# ATSAM3X8E_Main_Controller_-_TR.net
KiCad netlist of a schematic drawn in Altium Designer
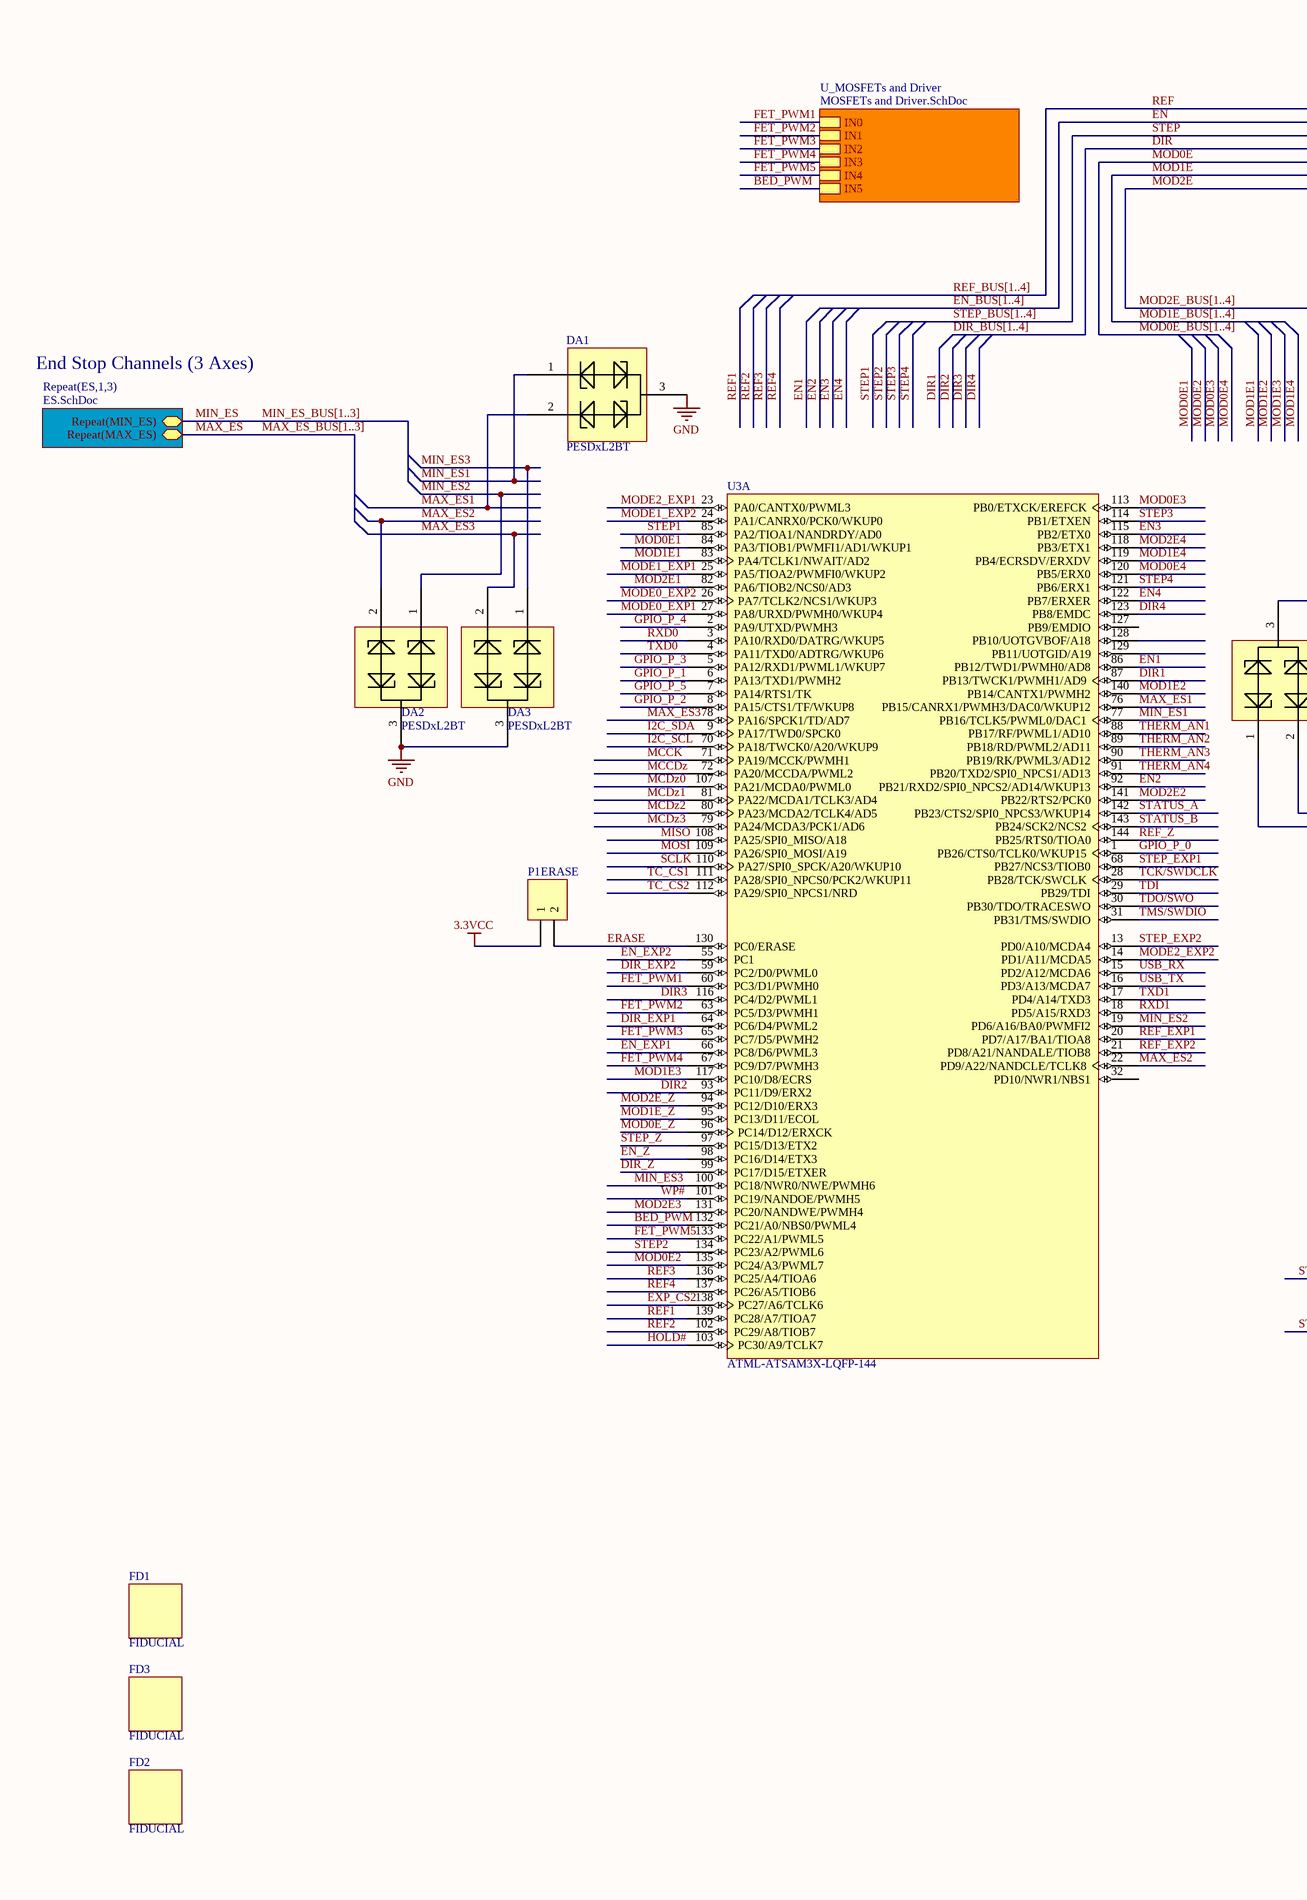
[diagram p0: ATSAM3X8E Main Controller - TR.SchDoc, left]
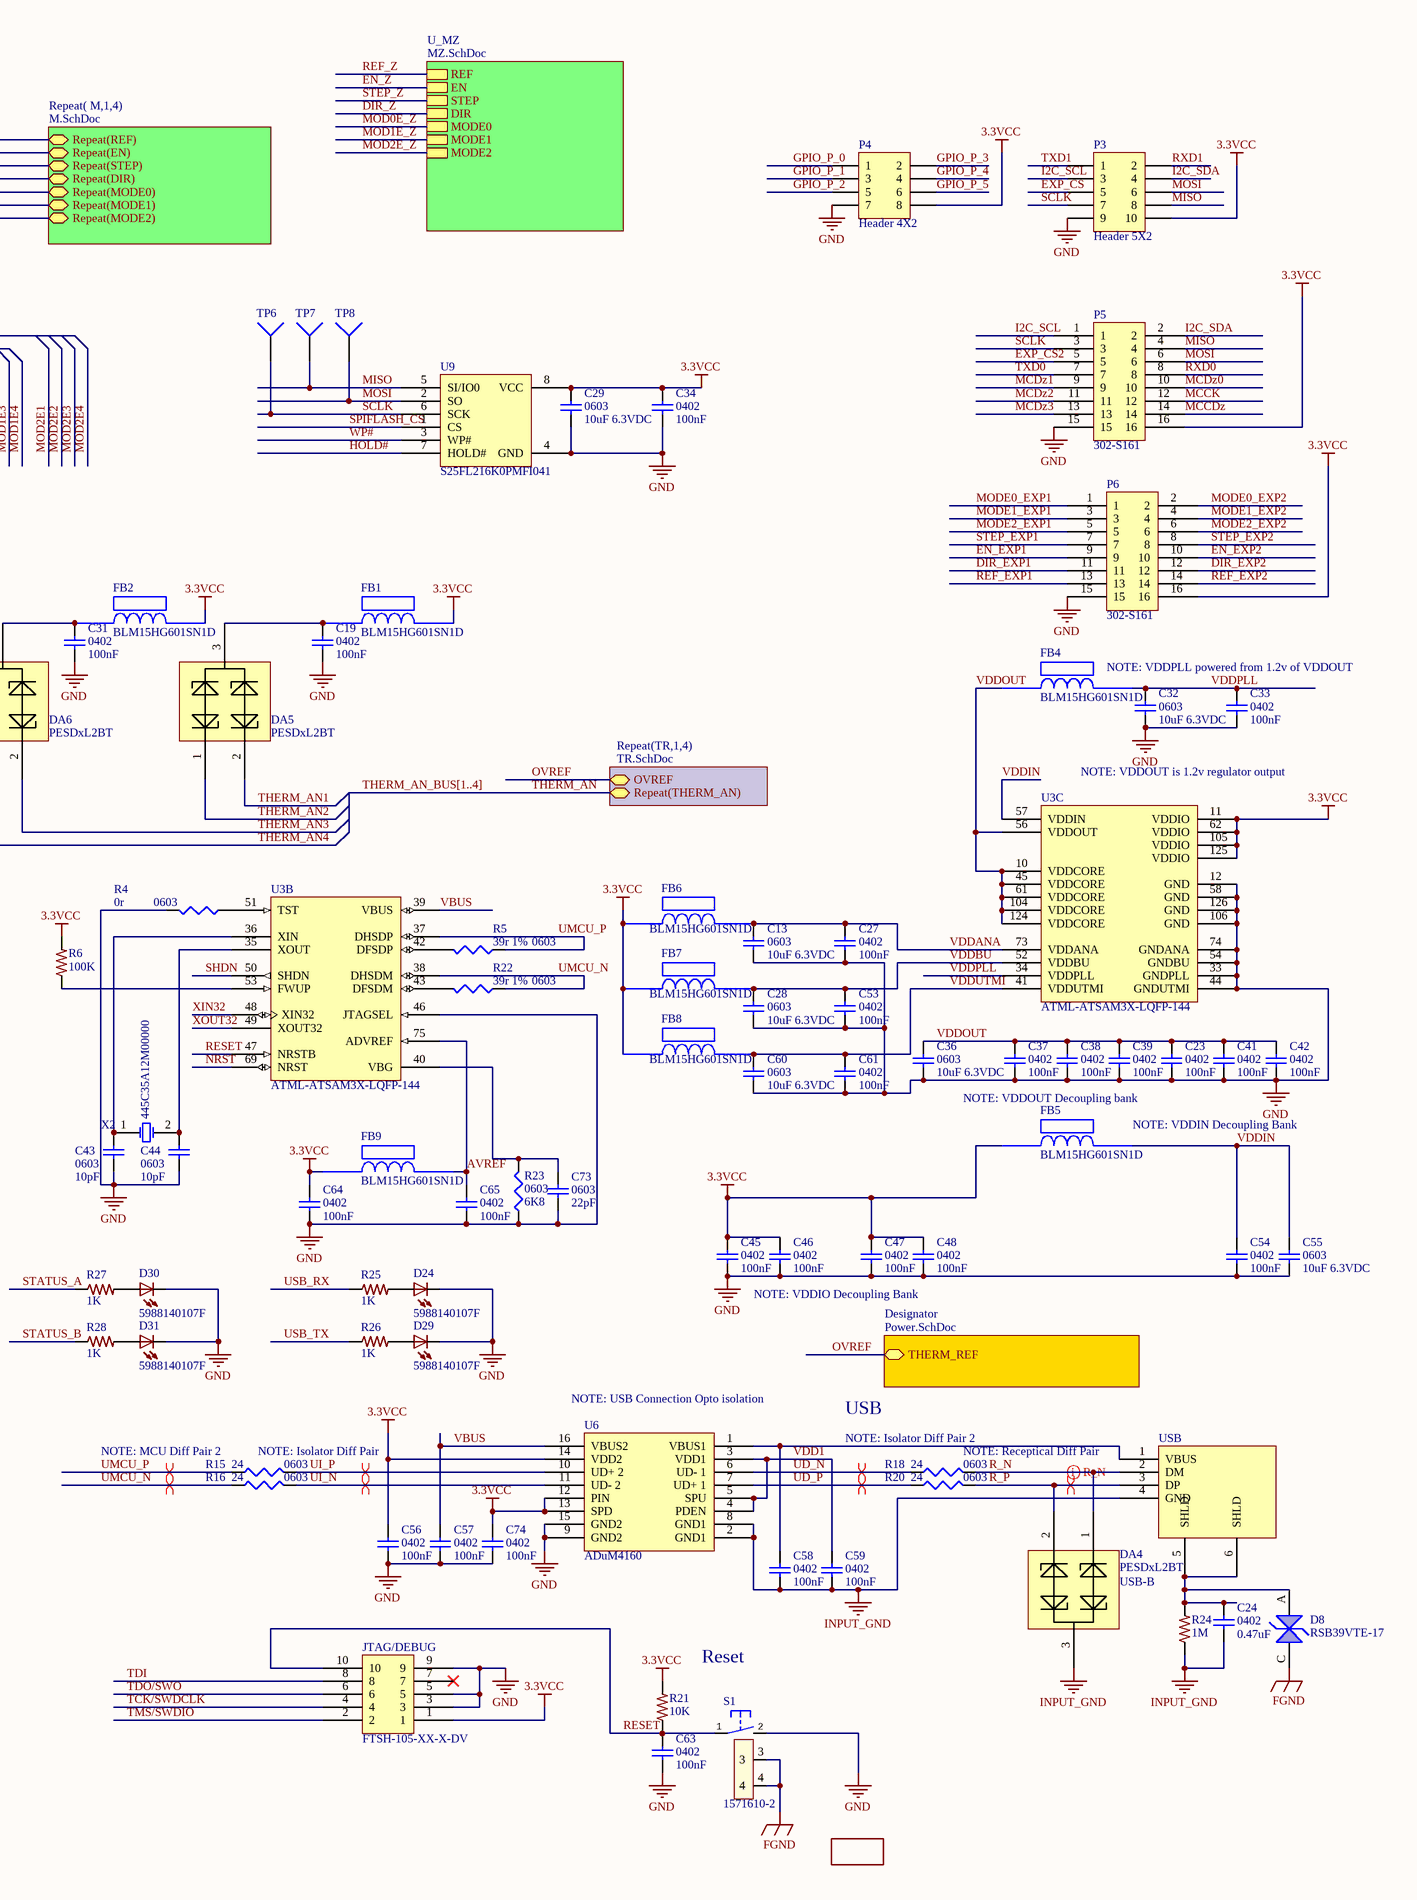
[diagram p1: ATSAM3X8E Main Controller - TR.SchDoc, right]

(export (version "E")
  (design (tool "Eeschema 10.0.6"))
  (components
    (comp (ref "C13")
      (value "0603")
      (footprint "C0603")
      (description "CAP CER 10UF 6.3V 10% JB 0603")
      (fields
        (field (name "MFR PART #") "C1608JB0J106K080AB")
        (field (name "MFR") "TDK")
        (field (name "ALTIUM_VALUE") "10uF 6.3VDC")
      )
      (libsource (lib "Tigershark3D") (part "C1608JB0J106K080AB"))
    )
    (comp (ref "C19")
      (value "100nF")
      (footprint "C0402")
      (description "Capacitor (Semiconductor SIM Model)")
      (fields
        (field (name "MFR PART #") "GRM155R71C104KA88D")
        (field (name "MFR") "Murata")
        (field (name "PACKAGEREFERENCE") "0402")
        (field (name "PUBLISHER") "Ultimachine")
      )
      (libsource (lib "Tigershark3D") (part "100nF C0402 - GRM155R71C104KA88D"))
    )
    (comp (ref "C23")
      (value "100nF")
      (footprint "C0402")
      (description "Capacitor (Semiconductor SIM Model)")
      (fields
        (field (name "MFR PART #") "GRM155R71C104KA88D")
        (field (name "MFR") "Murata")
        (field (name "PACKAGEREFERENCE") "0402")
        (field (name "PUBLISHER") "Ultimachine")
      )
      (libsource (lib "Tigershark3D") (part "100nF C0402 - GRM155R71C104KA88D"))
    )
    (comp (ref "C24")
      (value "0.47uF")
      (footprint "C0402")
      (description "0.47uF 6.3v C0402 - GRM155R60J474KE19D")
      (fields
        (field (name "MFR PART #") "GRM155R60J474KE19D")
        (field (name "MFR") "Murata")
        (field (name "PACKAGEREFERENCE") "0402")
        (field (name "PUBLISHER") "Ultimachine")
      )
      (libsource (lib "Tigershark3D") (part "GRM155R60J474KE19D"))
    )
    (comp (ref "C27")
      (value "100nF")
      (footprint "C0402")
      (description "Capacitor (Semiconductor SIM Model)")
      (fields
        (field (name "MFR PART #") "GRM155R71C104KA88D")
        (field (name "MFR") "Murata")
        (field (name "PACKAGEREFERENCE") "0402")
        (field (name "PUBLISHER") "Ultimachine")
      )
      (libsource (lib "Tigershark3D") (part "100nF C0402 - GRM155R71C104KA88D"))
    )
    (comp (ref "C28")
      (value "0603")
      (footprint "C0603")
      (description "CAP CER 10UF 6.3V 10% JB 0603")
      (fields
        (field (name "MFR PART #") "C1608JB0J106K080AB")
        (field (name "MFR") "TDK")
        (field (name "ALTIUM_VALUE") "10uF 6.3VDC")
      )
      (libsource (lib "Tigershark3D") (part "C1608JB0J106K080AB"))
    )
    (comp (ref "C29")
      (value "0603")
      (footprint "C0603")
      (description "CAP CER 10UF 6.3V 10% JB 0603")
      (fields
        (field (name "MFR PART #") "C1608JB0J106K080AB")
        (field (name "MFR") "TDK")
        (field (name "ALTIUM_VALUE") "10uF 6.3VDC")
      )
      (libsource (lib "Tigershark3D") (part "C1608JB0J106K080AB"))
    )
    (comp (ref "C31")
      (value "100nF")
      (footprint "C0402")
      (description "Capacitor (Semiconductor SIM Model)")
      (fields
        (field (name "MFR PART #") "GRM155R71C104KA88D")
        (field (name "MFR") "Murata")
        (field (name "PACKAGEREFERENCE") "0402")
        (field (name "PUBLISHER") "Ultimachine")
      )
      (libsource (lib "Tigershark3D") (part "100nF C0402 - GRM155R71C104KA88D"))
    )
    (comp (ref "C32")
      (value "0603")
      (footprint "C0603")
      (description "CAP CER 10UF 6.3V 10% JB 0603")
      (fields
        (field (name "MFR PART #") "C1608JB0J106K080AB")
        (field (name "MFR") "TDK")
        (field (name "ALTIUM_VALUE") "10uF 6.3VDC")
      )
      (libsource (lib "Tigershark3D") (part "C1608JB0J106K080AB"))
    )
    (comp (ref "C33")
      (value "100nF")
      (footprint "C0402")
      (description "Capacitor (Semiconductor SIM Model)")
      (fields
        (field (name "MFR PART #") "GRM155R71C104KA88D")
        (field (name "MFR") "Murata")
        (field (name "PACKAGEREFERENCE") "0402")
        (field (name "PUBLISHER") "Ultimachine")
      )
      (libsource (lib "Tigershark3D") (part "100nF C0402 - GRM155R71C104KA88D"))
    )
    (comp (ref "C34")
      (value "100nF")
      (footprint "C0402")
      (description "CAP CER 0.1UF (100nF) 16V 10% X7R 0402")
      (fields
        (field (name "MFR PART #") "GRM155R71C104KA88D")
        (field (name "MFR") "Murata")
        (field (name "PACKAGEREFERENCE") "0402")
        (field (name "PUBLISHER") "Ultimachine")
      )
      (libsource (lib "Tigershark3D") (part "GRM155R71C104KA88D"))
    )
    (comp (ref "C36")
      (value "0603")
      (footprint "C0603")
      (description "CAP CER 10UF 6.3V 10% JB 0603")
      (fields
        (field (name "MFR PART #") "C1608JB0J106K080AB")
        (field (name "MFR") "TDK")
        (field (name "ALTIUM_VALUE") "10uF 6.3VDC")
      )
      (libsource (lib "Tigershark3D") (part "C1608JB0J106K080AB"))
    )
    (comp (ref "C37")
      (value "100nF")
      (footprint "C0402")
      (description "Capacitor (Semiconductor SIM Model)")
      (fields
        (field (name "MFR PART #") "GRM155R71C104KA88D")
        (field (name "MFR") "Murata")
        (field (name "PACKAGEREFERENCE") "0402")
        (field (name "PUBLISHER") "Ultimachine")
      )
      (libsource (lib "Tigershark3D") (part "100nF C0402 - GRM155R71C104KA88D"))
    )
    (comp (ref "C38")
      (value "100nF")
      (footprint "C0402")
      (description "Capacitor (Semiconductor SIM Model)")
      (fields
        (field (name "MFR PART #") "GRM155R71C104KA88D")
        (field (name "MFR") "Murata")
        (field (name "PACKAGEREFERENCE") "0402")
        (field (name "PUBLISHER") "Ultimachine")
      )
      (libsource (lib "Tigershark3D") (part "100nF C0402 - GRM155R71C104KA88D"))
    )
    (comp (ref "C39")
      (value "100nF")
      (footprint "C0402")
      (description "Capacitor (Semiconductor SIM Model)")
      (fields
        (field (name "MFR PART #") "GRM155R71C104KA88D")
        (field (name "MFR") "Murata")
        (field (name "PACKAGEREFERENCE") "0402")
        (field (name "PUBLISHER") "Ultimachine")
      )
      (libsource (lib "Tigershark3D") (part "100nF C0402 - GRM155R71C104KA88D"))
    )
    (comp (ref "C41")
      (value "100nF")
      (footprint "C0402")
      (description "Capacitor (Semiconductor SIM Model)")
      (fields
        (field (name "MFR PART #") "GRM155R71C104KA88D")
        (field (name "MFR") "Murata")
        (field (name "PACKAGEREFERENCE") "0402")
        (field (name "PUBLISHER") "Ultimachine")
      )
      (libsource (lib "Tigershark3D") (part "100nF C0402 - GRM155R71C104KA88D"))
    )
    (comp (ref "C42")
      (value "100nF")
      (footprint "C0402")
      (description "Capacitor (Semiconductor SIM Model)")
      (fields
        (field (name "MFR PART #") "GRM155R71C104KA88D")
        (field (name "MFR") "Murata")
        (field (name "PACKAGEREFERENCE") "0402")
        (field (name "PUBLISHER") "Ultimachine")
      )
      (libsource (lib "Tigershark3D") (part "100nF C0402 - GRM155R71C104KA88D"))
    )
    (comp (ref "C43")
      (value "0603")
      (footprint "1608[0603]")
      (description "Capacitor (Semiconductor SIM Model)")
      (fields (field (name "ALTIUM_VALUE") "10pF") (field (name "PUBLISHER") "Altium Limited"))
      (libsource (lib "Miscellaneous Devices") (part "Cap Semi"))
    )
    (comp (ref "C44")
      (value "0603")
      (footprint "1608[0603]")
      (description "Capacitor (Semiconductor SIM Model)")
      (fields (field (name "ALTIUM_VALUE") "10pF") (field (name "PUBLISHER") "Altium Limited"))
      (libsource (lib "Miscellaneous Devices") (part "Cap Semi"))
    )
    (comp (ref "C45")
      (value "100nF")
      (footprint "C0402")
      (description "Capacitor (Semiconductor SIM Model)")
      (fields
        (field (name "MFR PART #") "GRM155R71C104KA88D")
        (field (name "MFR") "Murata")
        (field (name "PACKAGEREFERENCE") "0402")
        (field (name "PUBLISHER") "Ultimachine")
      )
      (libsource (lib "Tigershark3D") (part "100nF C0402 - GRM155R71C104KA88D"))
    )
    (comp (ref "C46")
      (value "100nF")
      (footprint "C0402")
      (description "Capacitor (Semiconductor SIM Model)")
      (fields
        (field (name "MFR PART #") "GRM155R71C104KA88D")
        (field (name "MFR") "Murata")
        (field (name "PACKAGEREFERENCE") "0402")
        (field (name "PUBLISHER") "Ultimachine")
      )
      (libsource (lib "Tigershark3D") (part "100nF C0402 - GRM155R71C104KA88D"))
    )
    (comp (ref "C47")
      (value "100nF")
      (footprint "C0402")
      (description "Capacitor (Semiconductor SIM Model)")
      (fields
        (field (name "MFR PART #") "GRM155R71C104KA88D")
        (field (name "MFR") "Murata")
        (field (name "PACKAGEREFERENCE") "0402")
        (field (name "PUBLISHER") "Ultimachine")
      )
      (libsource (lib "Tigershark3D") (part "100nF C0402 - GRM155R71C104KA88D"))
    )
    (comp (ref "C48")
      (value "100nF")
      (footprint "C0402")
      (description "Capacitor (Semiconductor SIM Model)")
      (fields
        (field (name "MFR PART #") "GRM155R71C104KA88D")
        (field (name "MFR") "Murata")
        (field (name "PACKAGEREFERENCE") "0402")
        (field (name "PUBLISHER") "Ultimachine")
      )
      (libsource (lib "Tigershark3D") (part "100nF C0402 - GRM155R71C104KA88D"))
    )
    (comp (ref "C53")
      (value "100nF")
      (footprint "C0402")
      (description "Capacitor (Semiconductor SIM Model)")
      (fields
        (field (name "MFR PART #") "GRM155R71C104KA88D")
        (field (name "MFR") "Murata")
        (field (name "PACKAGEREFERENCE") "0402")
        (field (name "PUBLISHER") "Ultimachine")
      )
      (libsource (lib "Tigershark3D") (part "100nF C0402 - GRM155R71C104KA88D"))
    )
    (comp (ref "C54")
      (value "100nF")
      (footprint "C0402")
      (description "Capacitor (Semiconductor SIM Model)")
      (fields
        (field (name "MFR PART #") "GRM155R71C104KA88D")
        (field (name "MFR") "Murata")
        (field (name "PACKAGEREFERENCE") "0402")
        (field (name "PUBLISHER") "Ultimachine")
      )
      (libsource (lib "Tigershark3D") (part "100nF C0402 - GRM155R71C104KA88D"))
    )
    (comp (ref "C55")
      (value "0603")
      (footprint "C0603")
      (description "CAP CER 10UF 6.3V 10% JB 0603")
      (fields
        (field (name "MFR PART #") "C1608JB0J106K080AB")
        (field (name "MFR") "TDK")
        (field (name "ALTIUM_VALUE") "10uF 6.3VDC")
      )
      (libsource (lib "Tigershark3D") (part "C1608JB0J106K080AB"))
    )
    (comp (ref "C56")
      (value "100nF")
      (footprint "C0402")
      (description "Capacitor (Semiconductor SIM Model)")
      (fields
        (field (name "MFR PART #") "GRM155R71C104KA88D")
        (field (name "MFR") "Murata")
        (field (name "PACKAGEREFERENCE") "0402")
        (field (name "PUBLISHER") "Ultimachine")
      )
      (libsource (lib "Tigershark3D") (part "100nF C0402 - GRM155R71C104KA88D"))
    )
    (comp (ref "C57")
      (value "100nF")
      (footprint "C0402")
      (description "Capacitor (Semiconductor SIM Model)")
      (fields
        (field (name "MFR PART #") "GRM155R71C104KA88D")
        (field (name "MFR") "Murata")
        (field (name "PACKAGEREFERENCE") "0402")
        (field (name "PUBLISHER") "Ultimachine")
      )
      (libsource (lib "Tigershark3D") (part "100nF C0402 - GRM155R71C104KA88D"))
    )
    (comp (ref "C58")
      (value "100nF")
      (footprint "C0402")
      (description "Capacitor (Semiconductor SIM Model)")
      (fields
        (field (name "MFR PART #") "GRM155R71C104KA88D")
        (field (name "MFR") "Murata")
        (field (name "PACKAGEREFERENCE") "0402")
        (field (name "PUBLISHER") "Ultimachine")
      )
      (libsource (lib "Tigershark3D") (part "100nF C0402 - GRM155R71C104KA88D"))
    )
    (comp (ref "C59")
      (value "100nF")
      (footprint "C0402")
      (description "Capacitor (Semiconductor SIM Model)")
      (fields
        (field (name "MFR PART #") "GRM155R71C104KA88D")
        (field (name "MFR") "Murata")
        (field (name "PACKAGEREFERENCE") "0402")
        (field (name "PUBLISHER") "Ultimachine")
      )
      (libsource (lib "Tigershark3D") (part "100nF C0402 - GRM155R71C104KA88D"))
    )
    (comp (ref "C60")
      (value "0603")
      (footprint "C0603")
      (description "CAP CER 10UF 6.3V 10% JB 0603")
      (fields
        (field (name "MFR PART #") "C1608JB0J106K080AB")
        (field (name "MFR") "TDK")
        (field (name "ALTIUM_VALUE") "10uF 6.3VDC")
      )
      (libsource (lib "Tigershark3D") (part "C1608JB0J106K080AB"))
    )
    (comp (ref "C61")
      (value "100nF")
      (footprint "C0402")
      (description "Capacitor (Semiconductor SIM Model)")
      (fields
        (field (name "MFR PART #") "GRM155R71C104KA88D")
        (field (name "MFR") "Murata")
        (field (name "PACKAGEREFERENCE") "0402")
        (field (name "PUBLISHER") "Ultimachine")
      )
      (libsource (lib "Tigershark3D") (part "100nF C0402 - GRM155R71C104KA88D"))
    )
    (comp (ref "C63")
      (value "100nF")
      (footprint "C0402")
      (description "Capacitor (Semiconductor SIM Model)")
      (fields
        (field (name "MFR PART #") "GRM155R71C104KA88D")
        (field (name "MFR") "Murata")
        (field (name "PACKAGEREFERENCE") "0402")
        (field (name "PUBLISHER") "Ultimachine")
      )
      (libsource (lib "Tigershark3D") (part "100nF C0402 - GRM155R71C104KA88D"))
    )
    (comp (ref "C64")
      (value "100nF")
      (footprint "C0402")
      (description "CAP CER 0.1UF (100nF) 16V 10% X7R 0402")
      (fields
        (field (name "MFR PART #") "GRM155R71C104KA88D")
        (field (name "MFR") "Murata")
        (field (name "PACKAGEREFERENCE") "0402")
        (field (name "PUBLISHER") "Ultimachine")
      )
      (libsource (lib "Tigershark3D") (part "GRM155R71C104KA88D"))
    )
    (comp (ref "C65")
      (value "100nF")
      (footprint "C0402")
      (description "CAP CER 0.1UF (100nF) 16V 10% X7R 0402")
      (fields
        (field (name "MFR PART #") "GRM155R71C104KA88D")
        (field (name "MFR") "Murata")
        (field (name "PACKAGEREFERENCE") "0402")
        (field (name "PUBLISHER") "Ultimachine")
      )
      (libsource (lib "Tigershark3D") (part "GRM155R71C104KA88D"))
    )
    (comp (ref "C73")
      (value "0603")
      (footprint "1608[0603]")
      (description "Capacitor (Semiconductor SIM Model)")
      (fields (field (name "ALTIUM_VALUE") "22pF") (field (name "PUBLISHER") "Altium Limited"))
      (libsource (lib "Miscellaneous Devices") (part "Cap Semi"))
    )
    (comp (ref "C74")
      (value "100nF")
      (footprint "C0402")
      (description "Capacitor (Semiconductor SIM Model)")
      (fields
        (field (name "MFR PART #") "GRM155R71C104KA88D")
        (field (name "MFR") "Murata")
        (field (name "PACKAGEREFERENCE") "0402")
        (field (name "PUBLISHER") "Ultimachine")
      )
      (libsource (lib "Tigershark3D") (part "100nF C0402 - GRM155R71C104KA88D"))
    )
    (comp (ref "D8")
      (value "RSB39VTE-17")
      (footprint "SOD323-R")
      (description "DIODE TVS")
      (libsource (lib "Tigershark3D") (part "RSB39VTE-17"))
    )
    (comp (ref "D24")
      (value "5988140107F")
      (footprint "LED2012120")
      (description "LED 0805 Yellow")
      (fields (field (name "PUBLISHER") "UltiMachine"))
      (libsource (lib "Tigershark3D") (part "5988140107F"))
    )
    (comp (ref "D29")
      (value "5988140107F")
      (footprint "LED2012120")
      (description "LED 0805 Yellow")
      (fields (field (name "PUBLISHER") "UltiMachine"))
      (libsource (lib "Tigershark3D") (part "5988140107F"))
    )
    (comp (ref "D30")
      (value "5988140107F")
      (footprint "LED2012120")
      (description "LED 0805 Yellow")
      (fields (field (name "PUBLISHER") "UltiMachine"))
      (libsource (lib "Tigershark3D") (part "5988140107F"))
    )
    (comp (ref "D31")
      (value "5988140107F")
      (footprint "LED2012120")
      (description "LED 0805 Yellow")
      (fields (field (name "PUBLISHER") "UltiMachine"))
      (libsource (lib "Tigershark3D") (part "5988140107F"))
    )
    (comp (ref "DA1")
      (value "PESDxL2BT")
      (footprint "SOT95P230X110-3N")
      (description "PESDxL2BT TVS Diode Array 2x")
      (libsource (lib "ZMBo Schematic Library") (part "PESDxL2BT"))
    )
    (comp (ref "DA2")
      (value "PESDxL2BT")
      (footprint "SOT95P230X110-3N")
      (description "PESDxL2BT TVS Diode Array 2x")
      (libsource (lib "") (part "PESDxL2BT_1"))
    )
    (comp (ref "DA3")
      (value "PESDxL2BT")
      (footprint "SOT95P230X110-3N")
      (description "PESDxL2BT TVS Diode Array 2x")
      (libsource (lib "") (part "PESDxL2BT_1"))
    )
    (comp (ref "DA4")
      (value "PESDxL2BT")
      (footprint "SOT95P230X110-3N")
      (description "PESDxL2BT TVS Diode Array 2x")
      (libsource (lib "") (part "PESDxL2BT_1"))
    )
    (comp (ref "DA5")
      (value "PESDxL2BT")
      (footprint "SOT95P230X110-3N")
      (description "PESDxL2BT TVS Diode Array 2x")
      (libsource (lib "") (part "PESDxL2BT_2"))
    )
    (comp (ref "DA6")
      (value "PESDxL2BT")
      (footprint "SOT95P230X110-3N")
      (description "PESDxL2BT TVS Diode Array 2x")
      (libsource (lib "") (part "PESDxL2BT_2"))
    )
    (comp (ref "FB1")
      (value "BLM15HG601SN1D")
      (footprint "BLM18PG121SN1D")
      (libsource (lib "AHD Part Library") (part "BLM15HG601SN1D"))
    )
    (comp (ref "FB2")
      (value "BLM15HG601SN1D")
      (footprint "BLM18PG121SN1D")
      (libsource (lib "AHD Part Library") (part "BLM15HG601SN1D"))
    )
    (comp (ref "FB4")
      (value "BLM15HG601SN1D")
      (footprint "BLM18PG121SN1D")
      (libsource (lib "AHD Part Library") (part "BLM15HG601SN1D"))
    )
    (comp (ref "FB5")
      (value "BLM15HG601SN1D")
      (footprint "BLM18PG121SN1D")
      (libsource (lib "AHD Part Library") (part "BLM15HG601SN1D"))
    )
    (comp (ref "FB6")
      (value "BLM15HG601SN1D")
      (footprint "BLM18PG121SN1D")
      (libsource (lib "AHD Part Library") (part "BLM15HG601SN1D"))
    )
    (comp (ref "FB7")
      (value "BLM15HG601SN1D")
      (footprint "BLM18PG121SN1D")
      (libsource (lib "AHD Part Library") (part "BLM15HG601SN1D"))
    )
    (comp (ref "FB8")
      (value "BLM15HG601SN1D")
      (footprint "BLM18PG121SN1D")
      (libsource (lib "AHD Part Library") (part "BLM15HG601SN1D"))
    )
    (comp (ref "FB9")
      (value "BLM15HG601SN1D")
      (footprint "BLM18PG121SN1D")
      (libsource (lib "AHD Part Library") (part "BLM15HG601SN1D"))
    )
    (comp (ref "FD1")
      (value "FIDUCIAL")
      (footprint "FIDUCIAL-1X2")
      (libsource (lib "ZMBo Schematic Library") (part "FIDUCIAL"))
    )
    (comp (ref "FD2")
      (value "FIDUCIAL")
      (footprint "FIDUCIAL-1X2")
      (libsource (lib "ZMBo Schematic Library") (part "FIDUCIAL"))
    )
    (comp (ref "FD3")
      (value "FIDUCIAL")
      (footprint "FIDUCIAL-1X2")
      (libsource (lib "ZMBo Schematic Library") (part "FIDUCIAL"))
    )
    (comp (ref "JTAG/DEBUG")
      (value "FTSH-105-XX-X-DV")
      (footprint "FTSH-105-XX-X-DV")
      (libsource (lib "Adams Altium Library") (part "ARM Cortex JTAG-DEBUG Header"))
    )
    (comp (ref "LOGO1")
      (value "OSHW_LOGO_8MILX0150-NT")
      (footprint "OSHW_8X150_NOTEXT")
      (fields (field (name "PUBLISHER") "UltiMachine"))
      (libsource (lib "3Delight") (part "OSHW_LOGO_8MILX0150-NT"))
    )
    (comp (ref "P1")
      (value "ERASE")
      (footprint "HDR1X2")
      (description "Header, 2-Pin")
      (fields (field (name "PUBLISHER") "Altium Limited"))
      (libsource (lib "Miscellaneous Connectors") (part "Header 2"))
    )
    (comp (ref "P3")
      (value "Header 5X2")
      (footprint "HDR2X5")
      (description "Header, 5-Pin, Dual row")
      (fields (field (name "PUBLISHER") "Altium Limited"))
      (libsource (lib "Miscellaneous Connectors") (part "Header 5X2"))
    )
    (comp (ref "P4")
      (value "Header 4X2")
      (footprint "HDR2X4")
      (description "Header, 4-Pin, Dual row")
      (fields (field (name "PUBLISHER") "Altium Limited"))
      (libsource (lib "Miscellaneous Connectors") (part "Header 4X2"))
    )
    (comp (ref "P5")
      (value "302-S161")
      (footprint "302-S161")
      (description "16 Pos 2.54mm Pin Connector Shrouded")
      (fields (field (name "DIGIKEY PART #") "ED10522-ND"))
      (libsource (lib "Tigershark3D") (part "302-S161"))
    )
    (comp (ref "P6")
      (value "302-S161")
      (footprint "302-S161")
      (description "16 Pos 2.54mm Pin Connector Shrouded")
      (fields (field (name "DIGIKEY PART #") "ED10522-ND"))
      (libsource (lib "Tigershark3D") (part "302-S161"))
    )
    (comp (ref "R4")
      (value "0603")
      (footprint "J1-0603")
      (description "Resistor")
      (fields (field (name "ALTIUM_VALUE") "0r") (field (name "PUBLISHER") "Altium Limited"))
      (libsource (lib "Miscellaneous Devices") (part "Res3"))
    )
    (comp (ref "R5")
      (value "0603")
      (footprint "J1-0603")
      (description "Resistor")
      (fields (field (name "ALTIUM_VALUE") "39r 1%") (field (name "PUBLISHER") "Altium Limited"))
      (libsource (lib "Miscellaneous Devices") (part "Res3"))
    )
    (comp (ref "R6")
      (value "100K")
      (footprint "R0603")
      (description "RES 100K OHM 1/10W 1% 0603 SMD")
      (fields
        (field (name "MANUFACTURERPARTNUMBER") "RC0603FR-07100KL")
        (field (name "PUBLISHER") "UltiMachine")
      )
      (libsource (lib "Tigershark3D") (part "RC0603FR-07100KL"))
    )
    (comp (ref "R15")
      (value "0603")
      (footprint "J1-0603")
      (description "Resistor")
      (fields (field (name "ALTIUM_VALUE") "24") (field (name "PUBLISHER") "Altium Limited"))
      (libsource (lib "Miscellaneous Devices") (part "Res3"))
    )
    (comp (ref "R16")
      (value "0603")
      (footprint "J1-0603")
      (description "Resistor")
      (fields (field (name "ALTIUM_VALUE") "24") (field (name "PUBLISHER") "Altium Limited"))
      (libsource (lib "Miscellaneous Devices") (part "Res3"))
    )
    (comp (ref "R18")
      (value "0603")
      (footprint "J1-0603")
      (description "Resistor")
      (fields (field (name "ALTIUM_VALUE") "24") (field (name "PUBLISHER") "Altium Limited"))
      (libsource (lib "Miscellaneous Devices") (part "Res3"))
    )
    (comp (ref "R20")
      (value "0603")
      (footprint "J1-0603")
      (description "Resistor")
      (fields (field (name "ALTIUM_VALUE") "24") (field (name "PUBLISHER") "Altium Limited"))
      (libsource (lib "Miscellaneous Devices") (part "Res3"))
    )
    (comp (ref "R21")
      (value "10K")
      (footprint "R0603")
      (description "RES 0603 10K 100mW 1%")
      (fields
        (field (name "MANUFACTURERPARTNUMBER") "ERJ-3EKF1002V")
        (field (name "PUBLISHER") "UltiMachine")
      )
      (libsource (lib "3Delight") (part "ERJ-3EKF1002V"))
    )
    (comp (ref "R22")
      (value "0603")
      (footprint "J1-0603")
      (description "Resistor")
      (fields (field (name "ALTIUM_VALUE") "39r 1%") (field (name "PUBLISHER") "Altium Limited"))
      (libsource (lib "Miscellaneous Devices") (part "Res3"))
    )
    (comp (ref "R23")
      (value "0603")
      (footprint "J1-0603")
      (description "Resistor")
      (fields (field (name "ALTIUM_VALUE") "6K8") (field (name "PUBLISHER") "Altium Limited"))
      (libsource (lib "Miscellaneous Devices") (part "Res3"))
    )
    (comp (ref "R24")
      (value "1M")
      (footprint "R0402")
      (description "RES 0402 1M 100mW 5%")
      (fields (field (name "MANUFACTURERPARTNUMBER") "ERJ2GEJ105X") (field (name "PUBLISHER") "UltiMachine"))
      (libsource (lib "Tigershark3D") (part "ERJ2GEJ105X"))
    )
    (comp (ref "R25")
      (value "1K")
      (footprint "R0603")
      (description "RES 0603 1K 100mW 1%")
      (fields
        (field (name "MANUFACTURERPARTNUMBER") "ERJ-3EKF1001V")
        (field (name "PUBLISHER") "UltiMachine")
      )
      (libsource (lib "Tigershark3D") (part "ERJ-3EKF1001V"))
    )
    (comp (ref "R26")
      (value "1K")
      (footprint "R0603")
      (description "RES 0603 1K 100mW 1%")
      (fields
        (field (name "MANUFACTURERPARTNUMBER") "ERJ-3EKF1001V")
        (field (name "PUBLISHER") "UltiMachine")
      )
      (libsource (lib "Tigershark3D") (part "ERJ-3EKF1001V"))
    )
    (comp (ref "R27")
      (value "1K")
      (footprint "R0603")
      (description "RES 0603 1K 100mW 1%")
      (fields
        (field (name "MANUFACTURERPARTNUMBER") "ERJ-3EKF1001V")
        (field (name "PUBLISHER") "UltiMachine")
      )
      (libsource (lib "Tigershark3D") (part "ERJ-3EKF1001V"))
    )
    (comp (ref "R28")
      (value "1K")
      (footprint "R0603")
      (description "RES 0603 1K 100mW 1%")
      (fields
        (field (name "MANUFACTURERPARTNUMBER") "ERJ-3EKF1001V")
        (field (name "PUBLISHER") "UltiMachine")
      )
      (libsource (lib "Tigershark3D") (part "ERJ-3EKF1001V"))
    )
    (comp (ref "S1")
      (value "1571610-2")
      (footprint "B3F-31XX")
      (description "SWTCH Momentary Washable")
      (fields
        (field (name "MANUFACTURER") "Omron")
        (field (name "MANUFACTURER_1") "TE")
        (field (name "PUBLISHER") "UltiMachine")
      )
      (libsource (lib "ZMBo Schematic Library") (part "1571610-2_1"))
    )
    (comp (ref "TP6")
      (value "TP4")
      (footprint "TP-2")
      (description "Socket")
      (fields (field (name "PUBLISHER") "Altium Limited"))
      (libsource (lib "ZMBo Schematic Library") (part "Socket"))
    )
    (comp (ref "TP7")
      (value "TP4")
      (footprint "TP-2")
      (description "Socket")
      (fields (field (name "PUBLISHER") "Altium Limited"))
      (libsource (lib "ZMBo Schematic Library") (part "Socket"))
    )
    (comp (ref "TP8")
      (value "TP4")
      (footprint "TP-2")
      (description "Socket")
      (fields (field (name "PUBLISHER") "Altium Limited"))
      (libsource (lib "ZMBo Schematic Library") (part "Socket"))
    )
    (comp (ref "U3")
      (value "ATML-ATSAM3X-LQFP-144")
      (footprint "LQFP144_N")
      (libsource (lib "ZMBo Schematic Library") (part "ATML-ATSAM3X-LQFP-144"))
    )
    (comp (ref "U6")
      (value "ADuM4160")
      (footprint "ADuM4160")
      (description "USB Opto Isolator")
      (libsource (lib "ZMBo Schematic Library") (part "ADuM4160"))
    )
    (comp (ref "U9")
      (value "S25FL216K0PMFI041")
      (footprint "S25FL216K0PMFI041")
      (fields (field (name "DIGIKEY PART NUMBER") "1274-1052-ND"))
      (libsource (lib "Tigershark3D") (part "S25FL216K0PMFI041"))
    )
    (comp (ref "USB")
      (value "USB-B")
      (footprint "PN61729")
      (libsource (lib "ZMBo Schematic Library") (part "USB-B"))
    )
    (comp (ref "X2")
      (value "445C35A12M00000")
      (footprint "445C35A12M00000")
      (description "Crystal Oscillator")
      (fields (field (name "PUBLISHER") "Altium Limited"))
      (libsource (lib "Miscellaneous Devices") (part "XTAL"))
    )
  )
  (nets
    (net (code "39") (name "/AVREF") (class "Default")
      (node (ref "C65") (pin "2") (pinfunction "2_2") (pintype "passive"))
      (node (ref "FB9") (pin "2") (pinfunction "2_2") (pintype "passive"))
      (node (ref "U3") (pin "75") (pinfunction "ADVREF_75") (pintype "input"))
    )
    (net (code "40") (name "/BED_PWM") (class "Default")
      (node (ref "U3") (pin "132") (pinfunction "PC21/A0/NBS0/PWML4_132") (pintype "bidirectional"))
    )
    (net (code "42") (name "/DIR1") (class "Default")
      (node (ref "U3") (pin "87") (pinfunction "PB13/TWCK1/PWMH1/AD9_87") (pintype "bidirectional"))
    )
    (net (code "43") (name "/DIR2") (class "Default")
      (node (ref "U3") (pin "93") (pinfunction "PC11/D9/ERX2_93") (pintype "bidirectional"))
    )
    (net (code "44") (name "/DIR3") (class "Default")
      (node (ref "U3") (pin "116") (pinfunction "PC4/D2/PWML1_116") (pintype "bidirectional"))
    )
    (net (code "45") (name "/DIR4") (class "Default")
      (node (ref "U3") (pin "123") (pinfunction "PB8/EMDC_123") (pintype "bidirectional"))
    )
    (net (code "47") (name "/DIR_EXP1") (class "Default")
      (node (ref "P6") (pin "11") (pinfunction "11_11") (pintype "passive"))
      (node (ref "U3") (pin "64") (pinfunction "PC6/D4/PWML2_64") (pintype "bidirectional"))
    )
    (net (code "48") (name "/DIR_EXP2") (class "Default")
      (node (ref "P6") (pin "12") (pinfunction "12_12") (pintype "passive"))
      (node (ref "U3") (pin "59") (pinfunction "PC2/D0/PWML0_59") (pintype "bidirectional"))
    )
    (net (code "49") (name "/DIR_Z") (class "Default")
      (node (ref "U3") (pin "99") (pinfunction "PC17/D15/ETXER_99") (pintype "bidirectional"))
    )
    (net (code "51") (name "/EN1") (class "Default")
      (node (ref "U3") (pin "86") (pinfunction "PB12/TWD1/PWMH0/AD8_86") (pintype "bidirectional"))
    )
    (net (code "52") (name "/EN2") (class "Default")
      (node (ref "U3") (pin "92") (pinfunction "PB21/RXD2/SPI0_NPCS2/AD14/WKUP13_92") (pintype "bidirectional"))
    )
    (net (code "53") (name "/EN3") (class "Default")
      (node (ref "U3") (pin "115") (pinfunction "PB2/ETX0_115") (pintype "bidirectional"))
    )
    (net (code "54") (name "/EN4") (class "Default")
      (node (ref "U3") (pin "122") (pinfunction "PB7/ERXER_122") (pintype "bidirectional"))
    )
    (net (code "56") (name "/EN_EXP1") (class "Default")
      (node (ref "P6") (pin "9") (pinfunction "9_9") (pintype "passive"))
      (node (ref "U3") (pin "66") (pinfunction "PC8/D6/PWML3_66") (pintype "bidirectional"))
    )
    (net (code "57") (name "/EN_EXP2") (class "Default")
      (node (ref "P6") (pin "10") (pinfunction "10_10") (pintype "passive"))
      (node (ref "U3") (pin "55") (pinfunction "PC1_55") (pintype "bidirectional"))
    )
    (net (code "58") (name "/EN_Z") (class "Default")
      (node (ref "U3") (pin "98") (pinfunction "PC16/D14/ETX3_98") (pintype "bidirectional"))
    )
    (net (code "59") (name "/ERASE") (class "Default")
      (node (ref "P1") (pin "2") (pinfunction "2_2") (pintype "passive"))
      (node (ref "U3") (pin "130") (pinfunction "PC0/ERASE_130") (pintype "bidirectional"))
    )
    (net (code "60") (name "/EXP_CS") (class "Default")
      (node (ref "P3") (pin "5") (pinfunction "5_5") (pintype "passive"))
    )
    (net (code "61") (name "/EXP_CS2") (class "Default")
      (node (ref "P5") (pin "5") (pinfunction "5_5") (pintype "passive"))
      (node (ref "U3") (pin "138") (pinfunction "PC27/A6/TCLK6_138") (pintype "bidirectional"))
    )
    (net (code "62") (name "/FET_PWM1") (class "Default")
      (node (ref "U3") (pin "60") (pinfunction "PC3/D1/PWMH0_60") (pintype "bidirectional"))
    )
    (net (code "63") (name "/FET_PWM2") (class "Default")
      (node (ref "U3") (pin "63") (pinfunction "PC5/D3/PWMH1_63") (pintype "bidirectional"))
    )
    (net (code "64") (name "/FET_PWM3") (class "Default")
      (node (ref "U3") (pin "65") (pinfunction "PC7/D5/PWMH2_65") (pintype "bidirectional"))
    )
    (net (code "65") (name "/FET_PWM4") (class "Default")
      (node (ref "U3") (pin "67") (pinfunction "PC9/D7/PWMH3_67") (pintype "bidirectional"))
    )
    (net (code "66") (name "/FET_PWM5") (class "Default")
      (node (ref "U3") (pin "133") (pinfunction "PC22/A1/PWML5_133") (pintype "bidirectional"))
    )
    (net (code "67") (name "/GPIO_P_0") (class "Default")
      (node (ref "P4") (pin "1") (pinfunction "1_1") (pintype "passive"))
      (node (ref "U3") (pin "1") (pinfunction "PB26/CTS0/TCLK0/WKUP15_1") (pintype "bidirectional"))
    )
    (net (code "68") (name "/GPIO_P_1") (class "Default")
      (node (ref "P4") (pin "3") (pinfunction "3_3") (pintype "passive"))
      (node (ref "U3") (pin "6") (pinfunction "PA13/TXD1/PWMH2_6") (pintype "bidirectional"))
    )
    (net (code "69") (name "/GPIO_P_2") (class "Default")
      (node (ref "P4") (pin "5") (pinfunction "5_5") (pintype "passive"))
      (node (ref "U3") (pin "8") (pinfunction "PA15/CTS1/TF/WKUP8_8") (pintype "bidirectional"))
    )
    (net (code "70") (name "/GPIO_P_3") (class "Default")
      (node (ref "P4") (pin "2") (pinfunction "2_2") (pintype "passive"))
      (node (ref "U3") (pin "5") (pinfunction "PA12/RXD1/PWML1/WKUP7_5") (pintype "bidirectional"))
    )
    (net (code "71") (name "/GPIO_P_4") (class "Default")
      (node (ref "P4") (pin "4") (pinfunction "4_4") (pintype "passive"))
      (node (ref "U3") (pin "2") (pinfunction "PA9/UTXD/PWMH3_2") (pintype "bidirectional"))
    )
    (net (code "72") (name "/GPIO_P_5") (class "Default")
      (node (ref "P4") (pin "6") (pinfunction "6_6") (pintype "passive"))
      (node (ref "U3") (pin "7") (pinfunction "PA14/RTS1/TK_7") (pintype "bidirectional"))
    )
    (net (code "73") (name "/HOLD#") (class "Default")
      (node (ref "U3") (pin "103") (pinfunction "PC30/A9/TCLK7_103") (pintype "bidirectional"))
      (node (ref "U9") (pin "7") (pinfunction "HOLD#_7") (pintype "passive"))
    )
    (net (code "74") (name "/I2C_SCL") (class "Default")
      (node (ref "P3") (pin "3") (pinfunction "3_3") (pintype "passive"))
      (node (ref "P5") (pin "1") (pinfunction "1_1") (pintype "passive"))
      (node (ref "U3") (pin "70") (pinfunction "PA18/TWCK0/A20/WKUP9_70") (pintype "bidirectional"))
    )
    (net (code "75") (name "/I2C_SDA") (class "Default")
      (node (ref "P3") (pin "4") (pinfunction "4_4") (pintype "passive"))
      (node (ref "P5") (pin "2") (pinfunction "2_2") (pintype "passive"))
      (node (ref "U3") (pin "9") (pinfunction "PA17/TWD0/SPCK0_9") (pintype "bidirectional"))
    )
    (net (code "77") (name "/MAX_ES1") (class "Default")
      (node (ref "DA1") (pin "2") (pinfunction "2_2") (pintype "passive"))
      (node (ref "U3") (pin "76") (pinfunction "PB15/CANRX1/PWMH3/DAC0/WKUP12_76") (pintype "bidirectional"))
    )
    (net (code "78") (name "/MAX_ES2") (class "Default")
      (node (ref "DA2") (pin "2") (pinfunction "2_2") (pintype "passive"))
      (node (ref "U3") (pin "22") (pinfunction "PD9/A22/NANDCLE/TCLK8_22") (pintype "bidirectional"))
    )
    (net (code "79") (name "/MAX_ES3") (class "Default")
      (node (ref "DA3") (pin "2") (pinfunction "2_2") (pintype "passive"))
      (node (ref "U3") (pin "78") (pinfunction "PA16/SPCK1/TD/AD7_78") (pintype "bidirectional"))
    )
    (net (code "81") (name "/MCCDz") (class "Default")
      (node (ref "P5") (pin "14") (pinfunction "14_14") (pintype "passive"))
      (node (ref "U3") (pin "72") (pinfunction "PA20/MCCDA/PWML2_72") (pintype "bidirectional"))
    )
    (net (code "82") (name "/MCCK") (class "Default")
      (node (ref "P5") (pin "12") (pinfunction "12_12") (pintype "passive"))
      (node (ref "U3") (pin "71") (pinfunction "PA19/MCCK/PWMH1_71") (pintype "bidirectional"))
    )
    (net (code "83") (name "/MCDz0") (class "Default")
      (node (ref "P5") (pin "10") (pinfunction "10_10") (pintype "passive"))
      (node (ref "U3") (pin "107") (pinfunction "PA21/MCDA0/PWML0_107") (pintype "bidirectional"))
    )
    (net (code "84") (name "/MCDz1") (class "Default")
      (node (ref "P5") (pin "9") (pinfunction "9_9") (pintype "passive"))
      (node (ref "U3") (pin "81") (pinfunction "PA22/MCDA1/TCLK3/AD4_81") (pintype "bidirectional"))
    )
    (net (code "85") (name "/MCDz2") (class "Default")
      (node (ref "P5") (pin "11") (pinfunction "11_11") (pintype "passive"))
      (node (ref "U3") (pin "80") (pinfunction "PA23/MCDA2/TCLK4/AD5_80") (pintype "bidirectional"))
    )
    (net (code "86") (name "/MCDz3") (class "Default")
      (node (ref "P5") (pin "13") (pinfunction "13_13") (pintype "passive"))
      (node (ref "U3") (pin "79") (pinfunction "PA24/MCDA3/PCK1/AD6_79") (pintype "bidirectional"))
    )
    (net (code "88") (name "/MIN_ES1") (class "Default")
      (node (ref "DA1") (pin "1") (pinfunction "1_1") (pintype "passive"))
      (node (ref "U3") (pin "77") (pinfunction "PB16/TCLK5/PWML0/DAC1_77") (pintype "bidirectional"))
    )
    (net (code "89") (name "/MIN_ES2") (class "Default")
      (node (ref "DA2") (pin "1") (pinfunction "1_1") (pintype "passive"))
      (node (ref "U3") (pin "19") (pinfunction "PD6/A16/BA0/PWMFI2_19") (pintype "bidirectional"))
    )
    (net (code "90") (name "/MIN_ES3") (class "Default")
      (node (ref "DA3") (pin "1") (pinfunction "1_1") (pintype "passive"))
      (node (ref "U3") (pin "100") (pinfunction "PC18/NWR0/NWE/PWMH6_100") (pintype "bidirectional"))
    )
    (net (code "92") (name "/MISO") (class "Default")
      (node (ref "P3") (pin "8") (pinfunction "8_8") (pintype "passive"))
      (node (ref "P5") (pin "4") (pinfunction "4_4") (pintype "passive"))
      (node (ref "TP7") (pin "1") (pinfunction "1_1") (pintype "passive"))
      (node (ref "U3") (pin "108") (pinfunction "PA25/SPI0_MISO/A18_108") (pintype "bidirectional"))
      (node (ref "U9") (pin "5") (pinfunction "SI/IO0_5") (pintype "passive"))
    )
    (net (code "94") (name "/MOD0E1") (class "Default")
      (node (ref "U3") (pin "84") (pinfunction "PA3/TIOB1/PWMFI1/AD1/WKUP1_84") (pintype "bidirectional"))
    )
    (net (code "95") (name "/MOD0E2") (class "Default")
      (node (ref "U3") (pin "135") (pinfunction "PC24/A3/PWML7_135") (pintype "bidirectional"))
    )
    (net (code "96") (name "/MOD0E3") (class "Default")
      (node (ref "U3") (pin "113") (pinfunction "PB0/ETXCK/EREFCK_113") (pintype "bidirectional"))
    )
    (net (code "97") (name "/MOD0E4") (class "Default")
      (node (ref "U3") (pin "120") (pinfunction "PB5/ERX0_120") (pintype "bidirectional"))
    )
    (net (code "99") (name "/MOD0E_Z") (class "Default")
      (node (ref "U3") (pin "96") (pinfunction "PC14/D12/ERXCK_96") (pintype "bidirectional"))
    )
    (net (code "101") (name "/MOD1E1") (class "Default")
      (node (ref "U3") (pin "83") (pinfunction "PA4/TCLK1/NWAIT/AD2_83") (pintype "bidirectional"))
    )
    (net (code "102") (name "/MOD1E2") (class "Default")
      (node (ref "U3") (pin "140") (pinfunction "PB14/CANTX1/PWMH2_140") (pintype "bidirectional"))
    )
    (net (code "103") (name "/MOD1E3") (class "Default")
      (node (ref "U3") (pin "117") (pinfunction "PC10/D8/ECRS_117") (pintype "bidirectional"))
    )
    (net (code "104") (name "/MOD1E4") (class "Default")
      (node (ref "U3") (pin "119") (pinfunction "PB4/ECRSDV/ERXDV_119") (pintype "bidirectional"))
    )
    (net (code "106") (name "/MOD1E_Z") (class "Default")
      (node (ref "U3") (pin "95") (pinfunction "PC13/D11/ECOL_95") (pintype "bidirectional"))
    )
    (net (code "108") (name "/MOD2E1") (class "Default")
      (node (ref "U3") (pin "82") (pinfunction "PA6/TIOB2/NCS0/AD3_82") (pintype "bidirectional"))
    )
    (net (code "109") (name "/MOD2E2") (class "Default")
      (node (ref "U3") (pin "141") (pinfunction "PB22/RTS2/PCK0_141") (pintype "bidirectional"))
    )
    (net (code "110") (name "/MOD2E3") (class "Default")
      (node (ref "U3") (pin "131") (pinfunction "PC20/NANDWE/PWMH4_131") (pintype "bidirectional"))
    )
    (net (code "111") (name "/MOD2E4") (class "Default")
      (node (ref "U3") (pin "118") (pinfunction "PB3/ETX1_118") (pintype "bidirectional"))
    )
    (net (code "113") (name "/MOD2E_Z") (class "Default")
      (node (ref "U3") (pin "94") (pinfunction "PC12/D10/ERX3_94") (pintype "bidirectional"))
    )
    (net (code "114") (name "/MODE0_EXP1") (class "Default")
      (node (ref "P6") (pin "1") (pinfunction "1_1") (pintype "passive"))
      (node (ref "U3") (pin "27") (pinfunction "PA8/URXD/PWMH0/WKUP4_27") (pintype "bidirectional"))
    )
    (net (code "115") (name "/MODE0_EXP2") (class "Default")
      (node (ref "P6") (pin "2") (pinfunction "2_2") (pintype "passive"))
      (node (ref "U3") (pin "26") (pinfunction "PA7/TCLK2/NCS1/WKUP3_26") (pintype "bidirectional"))
    )
    (net (code "116") (name "/MODE1_EXP1") (class "Default")
      (node (ref "P6") (pin "3") (pinfunction "3_3") (pintype "passive"))
      (node (ref "U3") (pin "25") (pinfunction "PA5/TIOA2/PWMFI0/WKUP2_25") (pintype "bidirectional"))
    )
    (net (code "117") (name "/MODE1_EXP2") (class "Default")
      (node (ref "P6") (pin "4") (pinfunction "4_4") (pintype "passive"))
      (node (ref "U3") (pin "24") (pinfunction "PA1/CANRX0/PCK0/WKUP0_24") (pintype "bidirectional"))
    )
    (net (code "118") (name "/MODE2_EXP1") (class "Default")
      (node (ref "P6") (pin "5") (pinfunction "5_5") (pintype "passive"))
      (node (ref "U3") (pin "23") (pinfunction "PA0/CANTX0/PWML3_23") (pintype "bidirectional"))
    )
    (net (code "119") (name "/MODE2_EXP2") (class "Default")
      (node (ref "P6") (pin "6") (pinfunction "6_6") (pintype "passive"))
      (node (ref "U3") (pin "14") (pinfunction "PD1/A11/MCDA5_14") (pintype "bidirectional"))
    )
    (net (code "120") (name "/MOSI") (class "Default")
      (node (ref "P3") (pin "6") (pinfunction "6_6") (pintype "passive"))
      (node (ref "P5") (pin "6") (pinfunction "6_6") (pintype "passive"))
      (node (ref "TP8") (pin "1") (pinfunction "1_1") (pintype "passive"))
      (node (ref "U3") (pin "109") (pinfunction "PA26/SPI0_MOSI/A19_109") (pintype "bidirectional"))
      (node (ref "U9") (pin "2") (pinfunction "SO_2") (pintype "passive"))
    )
    (net (code "121") (name "/NRST") (class "Default")
      (node (ref "U3") (pin "69") (pinfunction "NRST_69") (pintype "bidirectional"))
    )
    (net (code "124") (name "/REF1") (class "Default")
      (node (ref "U3") (pin "139") (pinfunction "PC28/A7/TIOA7_139") (pintype "bidirectional"))
    )
    (net (code "125") (name "/REF2") (class "Default")
      (node (ref "U3") (pin "102") (pinfunction "PC29/A8/TIOB7_102") (pintype "bidirectional"))
    )
    (net (code "126") (name "/REF3") (class "Default")
      (node (ref "U3") (pin "136") (pinfunction "PC25/A4/TIOA6_136") (pintype "bidirectional"))
    )
    (net (code "127") (name "/REF4") (class "Default")
      (node (ref "U3") (pin "137") (pinfunction "PC26/A5/TIOB6_137") (pintype "bidirectional"))
    )
    (net (code "129") (name "/REF_EXP1") (class "Default")
      (node (ref "P6") (pin "13") (pinfunction "13_13") (pintype "passive"))
      (node (ref "U3") (pin "20") (pinfunction "PD7/A17/BA1/TIOA8_20") (pintype "bidirectional"))
    )
    (net (code "130") (name "/REF_EXP2") (class "Default")
      (node (ref "P6") (pin "14") (pinfunction "14_14") (pintype "passive"))
      (node (ref "U3") (pin "21") (pinfunction "PD8/A21/NANDALE/TIOB8_21") (pintype "bidirectional"))
    )
    (net (code "131") (name "/REF_Z") (class "Default")
      (node (ref "U3") (pin "144") (pinfunction "PB25/RTS0/TIOA0_144") (pintype "bidirectional"))
    )
    (net (code "132") (name "/RESET") (class "Default")
      (node (ref "C63") (pin "2") (pinfunction "2_2") (pintype "passive"))
      (node (ref "JTAG/DEBUG") (pin "10") (pinfunction "10_10") (pintype "passive"))
      (node (ref "R21") (pin "1") (pinfunction "1_1") (pintype "passive"))
      (node (ref "S1") (pin "1") (pinfunction "P_1") (pintype "passive"))
      (node (ref "U3") (pin "47") (pinfunction "NRSTB_47") (pintype "input"))
    )
    (net (code "133") (name "/RXD0") (class "Default")
      (node (ref "P5") (pin "8") (pinfunction "8_8") (pintype "passive"))
      (node (ref "U3") (pin "3") (pinfunction "PA10/RXD0/DATRG/WKUP5_3") (pintype "bidirectional"))
    )
    (net (code "134") (name "/RXD1") (class "Default")
      (node (ref "P3") (pin "2") (pinfunction "2_2") (pintype "passive"))
      (node (ref "U3") (pin "18") (pinfunction "PD5/A15/RXD3_18") (pintype "bidirectional"))
    )
    (net (code "135") (name "/R_N") (class "Default")
      (node (ref "DA4") (pin "1") (pinfunction "1_1") (pintype "passive"))
      (node (ref "R18") (pin "2") (pinfunction "2_2") (pintype "passive"))
      (node (ref "USB") (pin "2") (pinfunction "DM_2") (pintype "passive"))
    )
    (net (code "136") (name "/R_P") (class "Default")
      (node (ref "DA4") (pin "2") (pinfunction "2_2") (pintype "passive"))
      (node (ref "R20") (pin "2") (pinfunction "2_2") (pintype "passive"))
      (node (ref "USB") (pin "3") (pinfunction "DP_3") (pintype "passive"))
    )
    (net (code "137") (name "/SCLK") (class "Default")
      (node (ref "P3") (pin "7") (pinfunction "7_7") (pintype "passive"))
      (node (ref "P5") (pin "3") (pinfunction "3_3") (pintype "passive"))
      (node (ref "TP6") (pin "1") (pinfunction "1_1") (pintype "passive"))
      (node (ref "U3") (pin "110") (pinfunction "PA27/SPI0_SPCK/A20/WKUP10_110") (pintype "bidirectional"))
      (node (ref "U9") (pin "6") (pinfunction "SCK_6") (pintype "passive"))
    )
    (net (code "138") (name "/SHDN") (class "Default")
      (node (ref "U3") (pin "50") (pinfunction "SHDN_50") (pintype "output"))
    )
    (net (code "139") (name "/SPIFLASH_CS") (class "Default")
      (node (ref "U9") (pin "1") (pinfunction "CS_1") (pintype "passive"))
    )
    (net (code "140") (name "/STATUS_A") (class "Default")
      (node (ref "R27") (pin "1") (pinfunction "1_1") (pintype "passive"))
      (node (ref "U3") (pin "142") (pinfunction "PB23/CTS2/SPI0_NPCS3/WKUP14_142") (pintype "bidirectional"))
    )
    (net (code "141") (name "/STATUS_B") (class "Default")
      (node (ref "R28") (pin "1") (pinfunction "1_1") (pintype "passive"))
      (node (ref "U3") (pin "143") (pinfunction "PB24/SCK2/NCS2_143") (pintype "bidirectional"))
    )
    (net (code "143") (name "/STEP1") (class "Default")
      (node (ref "U3") (pin "85") (pinfunction "PA2/TIOA1/NANDRDY/AD0_85") (pintype "bidirectional"))
    )
    (net (code "144") (name "/STEP2") (class "Default")
      (node (ref "U3") (pin "134") (pinfunction "PC23/A2/PWML6_134") (pintype "bidirectional"))
    )
    (net (code "145") (name "/STEP3") (class "Default")
      (node (ref "U3") (pin "114") (pinfunction "PB1/ETXEN_114") (pintype "bidirectional"))
    )
    (net (code "146") (name "/STEP4") (class "Default")
      (node (ref "U3") (pin "121") (pinfunction "PB6/ERX1_121") (pintype "bidirectional"))
    )
    (net (code "148") (name "/STEP_EXP1") (class "Default")
      (node (ref "P6") (pin "7") (pinfunction "7_7") (pintype "passive"))
      (node (ref "U3") (pin "68") (pinfunction "PB27/NCS3/TIOB0_68") (pintype "bidirectional"))
    )
    (net (code "149") (name "/STEP_EXP2") (class "Default")
      (node (ref "P6") (pin "8") (pinfunction "8_8") (pintype "passive"))
      (node (ref "U3") (pin "13") (pinfunction "PD0/A10/MCDA4_13") (pintype "bidirectional"))
    )
    (net (code "150") (name "/STEP_Z") (class "Default")
      (node (ref "U3") (pin "97") (pinfunction "PC15/D13/ETX2_97") (pintype "bidirectional"))
    )
    (net (code "151") (name "/TCK{slash}SWDCLK") (class "Default")
      (node (ref "JTAG/DEBUG") (pin "4") (pinfunction "4_4") (pintype "passive"))
      (node (ref "U3") (pin "28") (pinfunction "PB28/TCK/SWCLK_28") (pintype "bidirectional"))
    )
    (net (code "152") (name "/TC_CS1") (class "Default")
      (node (ref "U3") (pin "111") (pinfunction "PA28/SPI0_NPCS0/PCK2/WKUP11_111") (pintype "bidirectional"))
    )
    (net (code "153") (name "/TC_CS2") (class "Default")
      (node (ref "U3") (pin "112") (pinfunction "PA29/SPI0_NPCS1/NRD_112") (pintype "bidirectional"))
    )
    (net (code "154") (name "/TDI") (class "Default")
      (node (ref "JTAG/DEBUG") (pin "8") (pinfunction "8_8") (pintype "passive"))
      (node (ref "U3") (pin "29") (pinfunction "PB29/TDI_29") (pintype "bidirectional"))
    )
    (net (code "155") (name "/TDO{slash}SWO") (class "Default")
      (node (ref "JTAG/DEBUG") (pin "6") (pinfunction "6_6") (pintype "passive"))
      (node (ref "U3") (pin "30") (pinfunction "PB30/TDO/TRACESWO_30") (pintype "bidirectional"))
    )
    (net (code "157") (name "/THERM_AN1") (class "Default")
      (node (ref "DA5") (pin "2") (pinfunction "2_2") (pintype "passive"))
      (node (ref "U3") (pin "88") (pinfunction "PB17/RF/PWML1/AD10_88") (pintype "bidirectional"))
    )
    (net (code "158") (name "/THERM_AN2") (class "Default")
      (node (ref "DA5") (pin "1") (pinfunction "1_1") (pintype "passive"))
      (node (ref "U3") (pin "89") (pinfunction "PB18/RD/PWML2/AD11_89") (pintype "bidirectional"))
    )
    (net (code "159") (name "/THERM_AN3") (class "Default")
      (node (ref "DA6") (pin "2") (pinfunction "2_2") (pintype "passive"))
      (node (ref "U3") (pin "90") (pinfunction "PB19/RK/PWML3/AD12_90") (pintype "bidirectional"))
    )
    (net (code "160") (name "/THERM_AN4") (class "Default")
      (node (ref "DA6") (pin "1") (pinfunction "1_1") (pintype "passive"))
      (node (ref "U3") (pin "91") (pinfunction "PB20/TXD2/SPI0_NPCS1/AD13_91") (pintype "bidirectional"))
    )
    (net (code "162") (name "/TMS{slash}SWDIO") (class "Default")
      (node (ref "JTAG/DEBUG") (pin "2") (pinfunction "2_2") (pintype "passive"))
      (node (ref "U3") (pin "31") (pinfunction "PB31/TMS/SWDIO_31") (pintype "bidirectional"))
    )
    (net (code "163") (name "/TXD0") (class "Default")
      (node (ref "P5") (pin "7") (pinfunction "7_7") (pintype "passive"))
      (node (ref "U3") (pin "4") (pinfunction "PA11/TXD0/ADTRG/WKUP6_4") (pintype "bidirectional"))
    )
    (net (code "164") (name "/TXD1") (class "Default")
      (node (ref "P3") (pin "1") (pinfunction "1_1") (pintype "passive"))
      (node (ref "U3") (pin "17") (pinfunction "PD4/A14/TXD3_17") (pintype "bidirectional"))
    )
    (net (code "165") (name "/UD_N") (class "Default")
      (node (ref "R18") (pin "1") (pinfunction "1_1") (pintype "passive"))
      (node (ref "U6") (pin "6") (pinfunction "UD-_1_6") (pintype "passive"))
    )
    (net (code "166") (name "/UD_P") (class "Default")
      (node (ref "R20") (pin "1") (pinfunction "1_1") (pintype "passive"))
      (node (ref "U6") (pin "7") (pinfunction "UD+_1_7") (pintype "passive"))
    )
    (net (code "167") (name "/UI_N") (class "Default")
      (node (ref "R16") (pin "2") (pinfunction "2_2") (pintype "passive"))
      (node (ref "U6") (pin "11") (pinfunction "UD-_2_11") (pintype "passive"))
    )
    (net (code "168") (name "/UI_P") (class "Default")
      (node (ref "R15") (pin "2") (pinfunction "2_2") (pintype "passive"))
      (node (ref "U6") (pin "10") (pinfunction "UD+_2_10") (pintype "passive"))
    )
    (net (code "169") (name "/UMCU_N") (class "Default")
      (node (ref "R16") (pin "1") (pinfunction "1_1") (pintype "passive"))
      (node (ref "R22") (pin "1") (pinfunction "1_1") (pintype "passive"))
      (node (ref "U3") (pin "38") (pinfunction "DHSDM_38") (pintype "bidirectional"))
    )
    (net (code "170") (name "/UMCU_P") (class "Default")
      (node (ref "R15") (pin "1") (pinfunction "1_1") (pintype "passive"))
      (node (ref "R5") (pin "1") (pinfunction "1_1") (pintype "passive"))
      (node (ref "U3") (pin "37") (pinfunction "DHSDP_37") (pintype "bidirectional"))
    )
    (net (code "171") (name "/USB_RX") (class "Default")
      (node (ref "R25") (pin "1") (pinfunction "1_1") (pintype "passive"))
      (node (ref "U3") (pin "15") (pinfunction "PD2/A12/MCDA6_15") (pintype "bidirectional"))
    )
    (net (code "172") (name "/USB_TX") (class "Default")
      (node (ref "R26") (pin "1") (pinfunction "1_1") (pintype "passive"))
      (node (ref "U3") (pin "16") (pinfunction "PD3/A13/MCDA7_16") (pintype "bidirectional"))
    )
    (net (code "173") (name "/VBUS") (class "Default")
      (node (ref "C57") (pin "2") (pinfunction "2_2") (pintype "passive"))
      (node (ref "U3") (pin "39") (pinfunction "VBUS_39") (pintype "bidirectional"))
      (node (ref "U6") (pin "16") (pinfunction "VBUS2_16") (pintype "passive"))
    )
    (net (code "174") (name "/VDD1") (class "Default")
      (node (ref "C59") (pin "2") (pinfunction "2_2") (pintype "passive"))
      (node (ref "U6") (pin "3") (pinfunction "VDD1_3") (pintype "passive"))
      (node (ref "U6") (pin "4") (pinfunction "PDEN_4") (pintype "passive"))
      (node (ref "U6") (pin "5") (pinfunction "SPU_5") (pintype "passive"))
    )
    (net (code "175") (name "/VDDANA") (class "Default")
      (node (ref "C13") (pin "2") (pinfunction "2_2") (pintype "passive"))
      (node (ref "C27") (pin "2") (pinfunction "2_2") (pintype "passive"))
      (node (ref "FB6") (pin "2") (pinfunction "2_2") (pintype "passive"))
      (node (ref "U3") (pin "73") (pinfunction "VDDANA_73") (pintype "power_in"))
    )
    (net (code "176") (name "/VDDBU") (class "Default")
      (node (ref "C28") (pin "2") (pinfunction "2_2") (pintype "passive"))
      (node (ref "C53") (pin "2") (pinfunction "2_2") (pintype "passive"))
      (node (ref "FB7") (pin "2") (pinfunction "2_2") (pintype "passive"))
      (node (ref "U3") (pin "52") (pinfunction "VDDBU_52") (pintype "power_in"))
    )
    (net (code "177") (name "/VDDIN") (class "Default")
      (node (ref "C54") (pin "2") (pinfunction "2_2") (pintype "passive"))
      (node (ref "C55") (pin "2") (pinfunction "2_2") (pintype "passive"))
      (node (ref "FB5") (pin "2") (pinfunction "2_2") (pintype "passive"))
      (node (ref "U3") (pin "57") (pinfunction "VDDIN_57") (pintype "power_in"))
    )
    (net (code "178") (name "/VDDOUT") (class "Default")
      (node (ref "C23") (pin "2") (pinfunction "2_2") (pintype "passive"))
      (node (ref "C36") (pin "2") (pinfunction "2_2") (pintype "passive"))
      (node (ref "C37") (pin "2") (pinfunction "2_2") (pintype "passive"))
      (node (ref "C38") (pin "2") (pinfunction "2_2") (pintype "passive"))
      (node (ref "C39") (pin "2") (pinfunction "2_2") (pintype "passive"))
      (node (ref "C41") (pin "2") (pinfunction "2_2") (pintype "passive"))
      (node (ref "C42") (pin "2") (pinfunction "2_2") (pintype "passive"))
      (node (ref "FB4") (pin "1") (pinfunction "1_1") (pintype "passive"))
      (node (ref "U3") (pin "10") (pinfunction "VDDCORE_10") (pintype "power_in"))
      (node (ref "U3") (pin "104") (pinfunction "VDDCORE_104") (pintype "power_in"))
      (node (ref "U3") (pin "124") (pinfunction "VDDCORE_124") (pintype "power_in"))
      (node (ref "U3") (pin "45") (pinfunction "VDDCORE_45") (pintype "power_in"))
      (node (ref "U3") (pin "56") (pinfunction "VDDOUT_56") (pintype "power_in"))
      (node (ref "U3") (pin "61") (pinfunction "VDDCORE_61") (pintype "power_in"))
    )
    (net (code "179") (name "/VDDPLL") (class "Default")
      (node (ref "C32") (pin "2") (pinfunction "2_2") (pintype "passive"))
      (node (ref "C33") (pin "2") (pinfunction "2_2") (pintype "passive"))
      (node (ref "FB4") (pin "2") (pinfunction "2_2") (pintype "passive"))
      (node (ref "U3") (pin "34") (pinfunction "VDDPLL_34") (pintype "power_in"))
    )
    (net (code "180") (name "/VDDUTMI") (class "Default")
      (node (ref "C60") (pin "2") (pinfunction "2_2") (pintype "passive"))
      (node (ref "C61") (pin "2") (pinfunction "2_2") (pintype "passive"))
      (node (ref "FB8") (pin "2") (pinfunction "2_2") (pintype "passive"))
      (node (ref "U3") (pin "41") (pinfunction "VDDUTMI_41") (pintype "power_in"))
    )
    (net (code "181") (name "/WP#") (class "Default")
      (node (ref "U3") (pin "101") (pinfunction "PC19/NANDOE/PWMH5_101") (pintype "bidirectional"))
      (node (ref "U9") (pin "3") (pinfunction "WP#_3") (pintype "passive"))
    )
    (net (code "182") (name "/XIN32") (class "Default")
      (node (ref "U3") (pin "48") (pinfunction "XIN32_48") (pintype "bidirectional"))
    )
    (net (code "183") (name "/XOUT32") (class "Default")
      (node (ref "U3") (pin "49") (pinfunction "XOUT32_49") (pintype "passive"))
    )
    (net (code "184") (name "3.3VCC") (class "Default")
      (node (ref "C29") (pin "2") (pinfunction "2_2") (pintype "passive"))
      (node (ref "C34") (pin "2") (pinfunction "2_2") (pintype "passive"))
      (node (ref "C45") (pin "2") (pinfunction "2_2") (pintype "passive"))
      (node (ref "C46") (pin "2") (pinfunction "2_2") (pintype "passive"))
      (node (ref "C47") (pin "2") (pinfunction "2_2") (pintype "passive"))
      (node (ref "C48") (pin "2") (pinfunction "2_2") (pintype "passive"))
      (node (ref "C56") (pin "2") (pinfunction "2_2") (pintype "passive"))
      (node (ref "C64") (pin "2") (pinfunction "2_2") (pintype "passive"))
      (node (ref "C74") (pin "2") (pinfunction "2_2") (pintype "passive"))
      (node (ref "FB1") (pin "2") (pinfunction "2_2") (pintype "passive"))
      (node (ref "FB2") (pin "2") (pinfunction "2_2") (pintype "passive"))
      (node (ref "FB5") (pin "1") (pinfunction "1_1") (pintype "passive"))
      (node (ref "FB6") (pin "1") (pinfunction "1_1") (pintype "passive"))
      (node (ref "FB7") (pin "1") (pinfunction "1_1") (pintype "passive"))
      (node (ref "FB8") (pin "1") (pinfunction "1_1") (pintype "passive"))
      (node (ref "FB9") (pin "1") (pinfunction "1_1") (pintype "passive"))
      (node (ref "JTAG/DEBUG") (pin "1") (pinfunction "1_1") (pintype "passive"))
      (node (ref "P1") (pin "1") (pinfunction "1_1") (pintype "passive"))
      (node (ref "P3") (pin "10") (pinfunction "10_10") (pintype "passive"))
      (node (ref "P4") (pin "8") (pinfunction "8_8") (pintype "passive"))
      (node (ref "P5") (pin "16") (pinfunction "16_16") (pintype "passive"))
      (node (ref "P6") (pin "16") (pinfunction "16_16") (pintype "passive"))
      (node (ref "R21") (pin "2") (pinfunction "2_2") (pintype "passive"))
      (node (ref "R6") (pin "2") (pinfunction "2_2") (pintype "passive"))
      (node (ref "U3") (pin "105") (pinfunction "VDDIO_105") (pintype "power_in"))
      (node (ref "U3") (pin "11") (pinfunction "VDDIO_11") (pintype "power_in"))
      (node (ref "U3") (pin "125") (pinfunction "VDDIO_125") (pintype "power_in"))
      (node (ref "U3") (pin "62") (pinfunction "VDDIO_62") (pintype "power_in"))
      (node (ref "U6") (pin "12") (pinfunction "PIN_12") (pintype "passive"))
      (node (ref "U6") (pin "13") (pinfunction "SPD_13") (pintype "passive"))
      (node (ref "U6") (pin "14") (pinfunction "VDD2_14") (pintype "passive"))
      (node (ref "U9") (pin "8") (pinfunction "VCC_8") (pintype "passive"))
    )
    (net (code "185") (name "FGND") (class "Default")
      (node (ref "D8") (pin "C") (pinfunction "C_C") (pintype "power_in"))
      (node (ref "S1") (pin "3") (pinfunction "3_3") (pintype "power_in"))
      (node (ref "S1") (pin "4") (pinfunction "4_4") (pintype "power_in"))
    )
    (net (code "186") (name "GND") (class "Default")
      (node (ref "C13") (pin "1") (pinfunction "1_1") (pintype "passive"))
      (node (ref "C19") (pin "1") (pinfunction "1_1") (pintype "passive"))
      (node (ref "C23") (pin "1") (pinfunction "1_1") (pintype "passive"))
      (node (ref "C27") (pin "1") (pinfunction "1_1") (pintype "passive"))
      (node (ref "C28") (pin "1") (pinfunction "1_1") (pintype "passive"))
      (node (ref "C29") (pin "1") (pinfunction "1_1") (pintype "passive"))
      (node (ref "C31") (pin "1") (pinfunction "1_1") (pintype "passive"))
      (node (ref "C32") (pin "1") (pinfunction "1_1") (pintype "passive"))
      (node (ref "C33") (pin "1") (pinfunction "1_1") (pintype "passive"))
      (node (ref "C34") (pin "1") (pinfunction "1_1") (pintype "passive"))
      (node (ref "C36") (pin "1") (pinfunction "1_1") (pintype "passive"))
      (node (ref "C37") (pin "1") (pinfunction "1_1") (pintype "passive"))
      (node (ref "C38") (pin "1") (pinfunction "1_1") (pintype "passive"))
      (node (ref "C39") (pin "1") (pinfunction "1_1") (pintype "passive"))
      (node (ref "C41") (pin "1") (pinfunction "1_1") (pintype "passive"))
      (node (ref "C42") (pin "1") (pinfunction "1_1") (pintype "passive"))
      (node (ref "C43") (pin "1") (pinfunction "1_1") (pintype "passive"))
      (node (ref "C44") (pin "1") (pinfunction "1_1") (pintype "passive"))
      (node (ref "C45") (pin "1") (pinfunction "1_1") (pintype "passive"))
      (node (ref "C46") (pin "1") (pinfunction "1_1") (pintype "passive"))
      (node (ref "C47") (pin "1") (pinfunction "1_1") (pintype "passive"))
      (node (ref "C48") (pin "1") (pinfunction "1_1") (pintype "passive"))
      (node (ref "C53") (pin "1") (pinfunction "1_1") (pintype "passive"))
      (node (ref "C54") (pin "1") (pinfunction "1_1") (pintype "passive"))
      (node (ref "C55") (pin "1") (pinfunction "1_1") (pintype "passive"))
      (node (ref "C56") (pin "1") (pinfunction "1_1") (pintype "passive"))
      (node (ref "C57") (pin "1") (pinfunction "1_1") (pintype "passive"))
      (node (ref "C60") (pin "1") (pinfunction "1_1") (pintype "passive"))
      (node (ref "C61") (pin "1") (pinfunction "1_1") (pintype "passive"))
      (node (ref "C63") (pin "1") (pinfunction "1_1") (pintype "passive"))
      (node (ref "C64") (pin "1") (pinfunction "1_1") (pintype "passive"))
      (node (ref "C65") (pin "1") (pinfunction "1_1") (pintype "passive"))
      (node (ref "C73") (pin "1") (pinfunction "1_1") (pintype "passive"))
      (node (ref "C74") (pin "1") (pinfunction "1_1") (pintype "passive"))
      (node (ref "D24") (pin "C") (pinfunction "C_C") (pintype "passive"))
      (node (ref "D29") (pin "C") (pinfunction "C_C") (pintype "passive"))
      (node (ref "D30") (pin "C") (pinfunction "C_C") (pintype "passive"))
      (node (ref "D31") (pin "C") (pinfunction "C_C") (pintype "passive"))
      (node (ref "DA1") (pin "3") (pinfunction "3_3") (pintype "passive"))
      (node (ref "DA2") (pin "3") (pinfunction "3_3") (pintype "passive"))
      (node (ref "DA3") (pin "3") (pinfunction "3_3") (pintype "passive"))
      (node (ref "JTAG/DEBUG") (pin "3") (pinfunction "3_3") (pintype "passive"))
      (node (ref "JTAG/DEBUG") (pin "5") (pinfunction "5_5") (pintype "passive"))
      (node (ref "JTAG/DEBUG") (pin "9") (pinfunction "9_9") (pintype "passive"))
      (node (ref "P3") (pin "9") (pinfunction "9_9") (pintype "passive"))
      (node (ref "P4") (pin "7") (pinfunction "7_7") (pintype "passive"))
      (node (ref "P5") (pin "15") (pinfunction "15_15") (pintype "passive"))
      (node (ref "P6") (pin "15") (pinfunction "15_15") (pintype "passive"))
      (node (ref "R23") (pin "1") (pinfunction "1_1") (pintype "passive"))
      (node (ref "R4") (pin "2") (pinfunction "2_2") (pintype "passive"))
      (node (ref "S1") (pin "2") (pinfunction "S_2") (pintype "passive"))
      (node (ref "U3") (pin "106") (pinfunction "GND_106") (pintype "power_in"))
      (node (ref "U3") (pin "12") (pinfunction "GND_12") (pintype "power_in"))
      (node (ref "U3") (pin "126") (pinfunction "GND_126") (pintype "power_in"))
      (node (ref "U3") (pin "33") (pinfunction "GNDPLL_33") (pintype "power_in"))
      (node (ref "U3") (pin "44") (pinfunction "GNDUTMI_44") (pintype "power_in"))
      (node (ref "U3") (pin "46") (pinfunction "JTAGSEL_46") (pintype "input"))
      (node (ref "U3") (pin "54") (pinfunction "GNDBU_54") (pintype "power_in"))
      (node (ref "U3") (pin "58") (pinfunction "GND_58") (pintype "power_in"))
      (node (ref "U3") (pin "74") (pinfunction "GNDANA_74") (pintype "power_in"))
      (node (ref "U6") (pin "15") (pinfunction "GND2_15") (pintype "passive"))
      (node (ref "U6") (pin "9") (pinfunction "GND2_9") (pintype "passive"))
      (node (ref "U9") (pin "4") (pinfunction "GND_4") (pintype "passive"))
    )
    (net (code "187") (name "INPUT_GND") (class "Default")
      (node (ref "C24") (pin "1") (pinfunction "1_1") (pintype "passive"))
      (node (ref "C58") (pin "1") (pinfunction "1_1") (pintype "passive"))
      (node (ref "C59") (pin "1") (pinfunction "1_1") (pintype "passive"))
      (node (ref "DA4") (pin "3") (pinfunction "3_3") (pintype "passive"))
      (node (ref "R24") (pin "1") (pinfunction "1_1") (pintype "passive"))
      (node (ref "U6") (pin "2") (pinfunction "GND1_2") (pintype "passive"))
      (node (ref "U6") (pin "8") (pinfunction "GND1_8") (pintype "passive"))
      (node (ref "USB") (pin "4") (pinfunction "GND_4") (pintype "passive"))
    )
    (net (code "188") (name "Net-(C19-Pad2)") (class "Default")
      (node (ref "C19") (pin "2") (pinfunction "2_2") (pintype "passive"))
      (node (ref "DA5") (pin "3") (pinfunction "3_3") (pintype "passive"))
      (node (ref "FB1") (pin "1") (pinfunction "1_1") (pintype "passive"))
    )
    (net (code "189") (name "Net-(C24-Pad2)") (class "Default")
      (node (ref "C24") (pin "2") (pinfunction "2_2") (pintype "passive"))
      (node (ref "D8") (pin "A") (pinfunction "A_A") (pintype "power_in"))
      (node (ref "R24") (pin "2") (pinfunction "2_2") (pintype "passive"))
      (node (ref "USB") (pin "5") (pinfunction "SHLD_5") (pintype "passive"))
      (node (ref "USB") (pin "6") (pinfunction "SHLD_6") (pintype "passive"))
    )
    (net (code "190") (name "Net-(C31-Pad2)") (class "Default")
      (node (ref "C31") (pin "2") (pinfunction "2_2") (pintype "passive"))
      (node (ref "DA6") (pin "3") (pinfunction "3_3") (pintype "passive"))
      (node (ref "FB2") (pin "1") (pinfunction "1_1") (pintype "passive"))
    )
    (net (code "191") (name "Net-(D24-PadA)") (class "Default")
      (node (ref "D24") (pin "A") (pinfunction "A_A") (pintype "passive"))
      (node (ref "R25") (pin "2") (pinfunction "2_2") (pintype "passive"))
    )
    (net (code "192") (name "Net-(D29-PadA)") (class "Default")
      (node (ref "D29") (pin "A") (pinfunction "A_A") (pintype "passive"))
      (node (ref "R26") (pin "2") (pinfunction "2_2") (pintype "passive"))
    )
    (net (code "193") (name "Net-(D30-PadA)") (class "Default")
      (node (ref "D30") (pin "A") (pinfunction "A_A") (pintype "passive"))
      (node (ref "R27") (pin "2") (pinfunction "2_2") (pintype "passive"))
    )
    (net (code "194") (name "Net-(D31-PadA)") (class "Default")
      (node (ref "D31") (pin "A") (pinfunction "A_A") (pintype "passive"))
      (node (ref "R28") (pin "2") (pinfunction "2_2") (pintype "passive"))
    )
    (net (code "195") (name "Net-(U3B-DFSDM)") (class "Default")
      (node (ref "R22") (pin "2") (pinfunction "2_2") (pintype "passive"))
      (node (ref "U3") (pin "43") (pinfunction "DFSDM_43") (pintype "bidirectional"))
    )
    (net (code "196") (name "Net-(U3B-DFSDP)") (class "Default")
      (node (ref "R5") (pin "2") (pinfunction "2_2") (pintype "passive"))
      (node (ref "U3") (pin "42") (pinfunction "DFSDP_42") (pintype "bidirectional"))
    )
    (net (code "197") (name "Net-(U3B-FWUP)") (class "Default")
      (node (ref "R6") (pin "1") (pinfunction "1_1") (pintype "passive"))
      (node (ref "U3") (pin "53") (pinfunction "FWUP_53") (pintype "input"))
    )
    (net (code "198") (name "Net-(U3B-TST)") (class "Default")
      (node (ref "R4") (pin "1") (pinfunction "1_1") (pintype "passive"))
      (node (ref "U3") (pin "51") (pinfunction "TST_51") (pintype "input"))
    )
    (net (code "199") (name "Net-(U3B-VBG)") (class "Default")
      (node (ref "C73") (pin "2") (pinfunction "2_2") (pintype "passive"))
      (node (ref "R23") (pin "2") (pinfunction "2_2") (pintype "passive"))
      (node (ref "U3") (pin "40") (pinfunction "VBG_40") (pintype "passive"))
    )
    (net (code "200") (name "Net-(U3B-XIN)") (class "Default")
      (node (ref "C43") (pin "2") (pinfunction "2_2") (pintype "passive"))
      (node (ref "U3") (pin "36") (pinfunction "XIN_36") (pintype "passive"))
      (node (ref "X2") (pin "1") (pinfunction "OSC1_1") (pintype "passive"))
    )
    (net (code "201") (name "Net-(U3B-XOUT)") (class "Default")
      (node (ref "C44") (pin "2") (pinfunction "2_2") (pintype "passive"))
      (node (ref "U3") (pin "35") (pinfunction "XOUT_35") (pintype "passive"))
      (node (ref "X2") (pin "2") (pinfunction "OSC2_2") (pintype "passive"))
    )
    (net (code "202") (name "Net-(U6-VBUS1)") (class "Default")
      (node (ref "C58") (pin "2") (pinfunction "2_2") (pintype "passive"))
      (node (ref "U6") (pin "1") (pinfunction "VBUS1_1") (pintype "passive"))
      (node (ref "USB") (pin "1") (pinfunction "VBUS_1") (pintype "passive"))
    )
    (net (code "203") (name "unconnected-(JTAG/DEBUG-Pad7)") (class "Default")
      (node (ref "JTAG/DEBUG") (pin "7") (pinfunction "7_7") (pintype "passive+no_connect"))
    )
    (net (code "204") (name "unconnected-(U3A-PB9{slash}EMDIO-Pad127)") (class "Default")
      (node (ref "U3") (pin "127") (pinfunction "PB9/EMDIO_127") (pintype "bidirectional"))
    )
    (net (code "205") (name "unconnected-(U3A-PB10{slash}UOTGVBOF{slash}A18-Pad128)") (class "Default")
      (node (ref "U3") (pin "128") (pinfunction "PB10/UOTGVBOF/A18_128") (pintype "bidirectional"))
    )
    (net (code "206") (name "unconnected-(U3A-PB11{slash}UOTGID{slash}A19-Pad129)") (class "Default")
      (node (ref "U3") (pin "129") (pinfunction "PB11/UOTGID/A19_129") (pintype "bidirectional"))
    )
    (net (code "207") (name "unconnected-(U3A-PD10{slash}NWR1{slash}NBS1-Pad32)") (class "Default")
      (node (ref "U3") (pin "32") (pinfunction "PD10/NWR1/NBS1_32") (pintype "bidirectional"))
    )
  )
)
